# Triac-Board.net
KiCad netlist of a schematic drawn in EAGLE
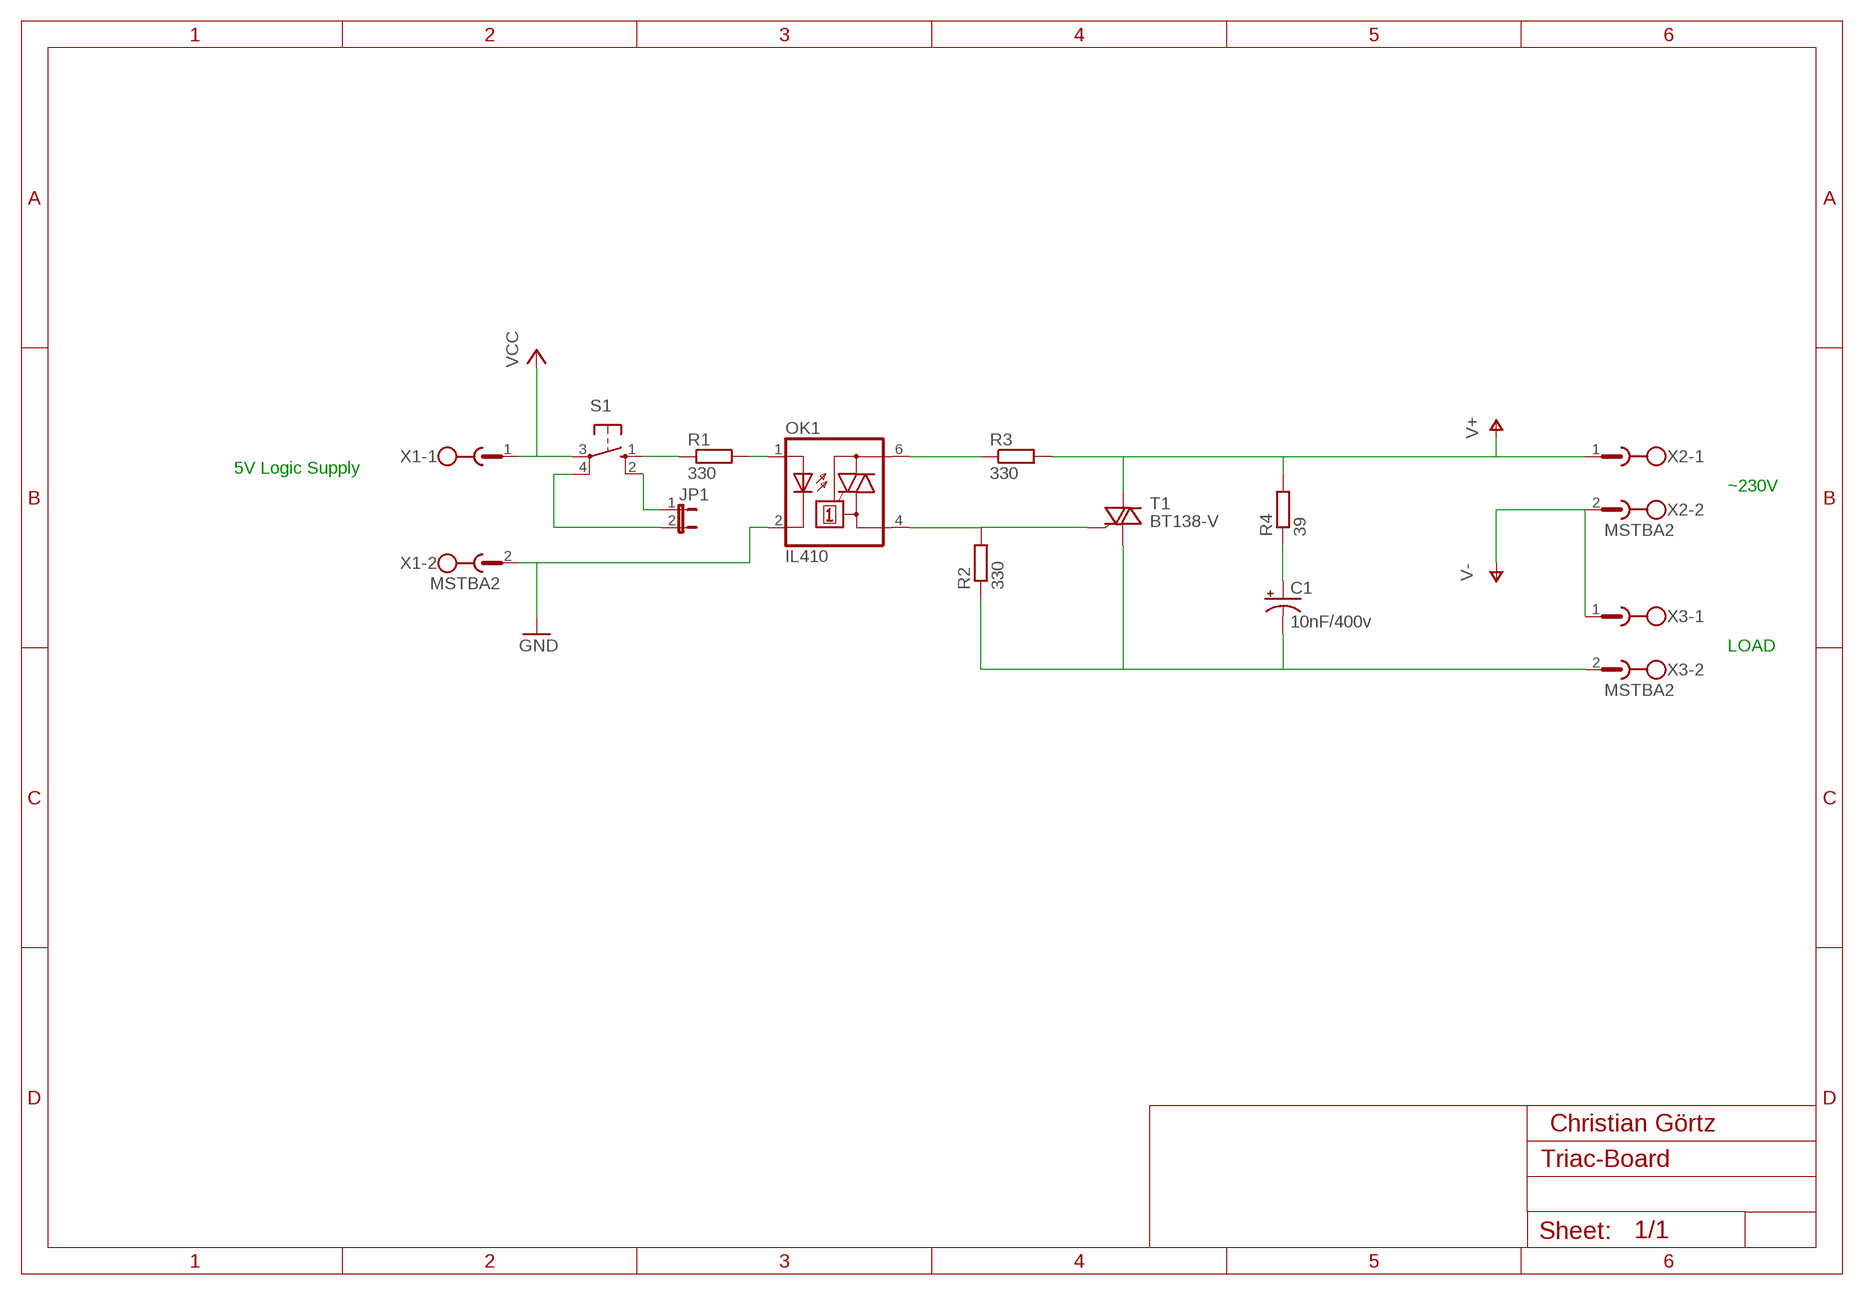
[diagram p0: schematic, sheet 1]

(export (version "E")
  (design (tool "Eeschema 10.0.6"))
  (components
    (comp (ref "C1")
      (value "10nF/400v")
      (footprint "eagle-import:E5-5")
      (libsource (lib "eagle-import") (part "CPOL-USE5-5"))
    )
    (comp (ref "JP1")
      (value "JP1E")
      (footprint "eagle-import:JP1")
      (libsource (lib "eagle-import") (part "JP1E"))
    )
    (comp (ref "OK1")
      (value "IL410")
      (footprint "eagle-import:DIL06")
      (fields (field (name "MF") "VISHAY/TELEFUNKEN"))
      (libsource (lib "eagle-import") (part "IL410"))
    )
    (comp (ref "R1")
      (value "330")
      (footprint "eagle-import:0207_12")
      (libsource (lib "eagle-import") (part "R-EU_0207/12"))
    )
    (comp (ref "R2")
      (value "330")
      (footprint "eagle-import:0207_12")
      (libsource (lib "eagle-import") (part "R-EU_0207/12"))
    )
    (comp (ref "R3")
      (value "330")
      (footprint "eagle-import:0207_12")
      (libsource (lib "eagle-import") (part "R-EU_0207/12"))
    )
    (comp (ref "R4")
      (value "39")
      (footprint "eagle-import:0207_12")
      (libsource (lib "eagle-import") (part "R-EU_0207/12"))
    )
    (comp (ref "S1")
      (value "10-XX")
      (footprint "eagle-import:B3F-10XX")
      (fields (field (name "MPN") "B3F-1000"))
      (libsource (lib "eagle-import") (part "10-XX"))
    )
    (comp (ref "T1")
      (value "BT138-V")
      (footprint "eagle-import:TO220BV")
      (libsource (lib "eagle-import") (part "BT138-V"))
    )
    (comp (ref "X1")
      (value "MSTBA2")
      (footprint "eagle-import:MSTBA2")
      (fields (field (name "MF") "FARNELL") (field (name "MPN") "1757242"))
      (libsource (lib "eagle-import") (part "MSTBA2"))
    )
    (comp (ref "X2")
      (value "MSTBA2")
      (footprint "eagle-import:MSTBA2")
      (fields (field (name "MF") "FARNELL") (field (name "MPN") "1757242"))
      (libsource (lib "eagle-import") (part "MSTBA2"))
    )
    (comp (ref "X3")
      (value "MSTBA2")
      (footprint "eagle-import:MSTBA2")
      (fields (field (name "MF") "FARNELL") (field (name "MPN") "1757242"))
      (libsource (lib "eagle-import") (part "MSTBA2"))
    )
  )
  (nets
    (net (code "1") (name "GND") (class "Default")
      (node (ref "OK1") (pin "2") (pinfunction "C_2") (pintype "passive"))
      (node (ref "X1") (pin "2") (pinfunction "1_2") (pintype "passive"))
    )
    (net (code "2") (name "Net-(C1-Pad+)") (class "Default")
      (node (ref "C1") (pin "+") (pinfunction "+_+") (pintype "passive"))
      (node (ref "R4") (pin "1") (pinfunction "1_1") (pintype "passive"))
    )
    (net (code "3") (name "Net-(OK1-A)") (class "Default")
      (node (ref "OK1") (pin "1") (pinfunction "A_1") (pintype "passive"))
      (node (ref "R1") (pin "2") (pinfunction "2_2") (pintype "passive"))
    )
    (net (code "4") (name "Net-(OK1-A1)") (class "Default")
      (node (ref "OK1") (pin "4") (pinfunction "A1_4") (pintype "passive"))
      (node (ref "R2") (pin "2") (pinfunction "2_2") (pintype "passive"))
      (node (ref "T1") (pin "G") (pinfunction "G_G") (pintype "passive"))
    )
    (net (code "5") (name "Net-(OK1-A2)") (class "Default")
      (node (ref "OK1") (pin "6") (pinfunction "A2_6") (pintype "passive"))
      (node (ref "R3") (pin "1") (pinfunction "1_1") (pintype "passive"))
    )
    (net (code "6") (name "Net-(S1-P1)") (class "Default")
      (node (ref "JP1") (pin "2") (pinfunction "2_2") (pintype "passive"))
      (node (ref "S1") (pin "4") (pinfunction "P1_4") (pintype "passive"))
    )
    (net (code "7") (name "Net-(S1-S)") (class "Default")
      (node (ref "R1") (pin "1") (pinfunction "1_1") (pintype "passive"))
      (node (ref "S1") (pin "1") (pinfunction "S_1") (pintype "passive"))
    )
    (net (code "8") (name "Net-(S1-S1)") (class "Default")
      (node (ref "JP1") (pin "1") (pinfunction "1_1") (pintype "passive"))
      (node (ref "S1") (pin "2") (pinfunction "S1_2") (pintype "passive"))
    )
    (net (code "9") (name "Net-(T1-A1)") (class "Default")
      (node (ref "C1") (pin "-") (pinfunction "-_-") (pintype "passive"))
      (node (ref "R2") (pin "1") (pinfunction "1_1") (pintype "passive"))
      (node (ref "T1") (pin "T1") (pinfunction "A1_T1") (pintype "passive"))
      (node (ref "X3") (pin "2") (pinfunction "1_2") (pintype "passive"))
    )
    (net (code "10") (name "V+") (class "Default")
      (node (ref "R3") (pin "2") (pinfunction "2_2") (pintype "passive"))
      (node (ref "R4") (pin "2") (pinfunction "2_2") (pintype "passive"))
      (node (ref "T1") (pin "T2") (pinfunction "A2_T2") (pintype "passive"))
      (node (ref "X2") (pin "1") (pinfunction "1_1") (pintype "passive"))
    )
    (net (code "11") (name "V-") (class "Default")
      (node (ref "X2") (pin "2") (pinfunction "1_2") (pintype "passive"))
      (node (ref "X3") (pin "1") (pinfunction "1_1") (pintype "passive"))
    )
    (net (code "12") (name "VCC") (class "Default")
      (node (ref "S1") (pin "3") (pinfunction "P_3") (pintype "passive"))
      (node (ref "X1") (pin "1") (pinfunction "1_1") (pintype "passive"))
    )
  )
)
